# pay-optical.net
KiCad netlist of a schematic drawn in Altium Designer
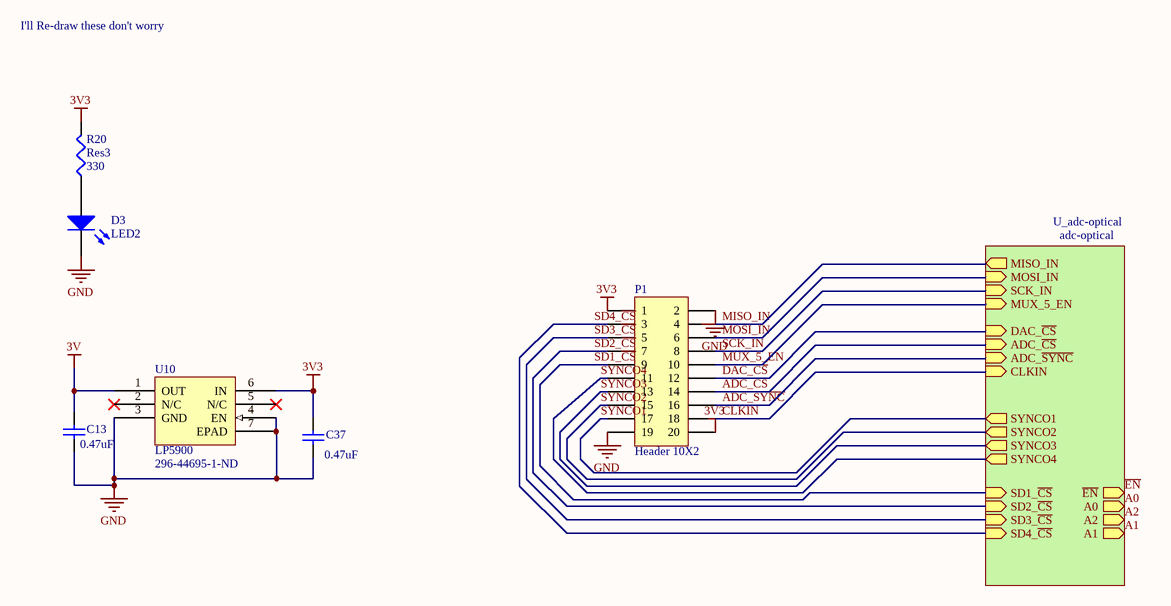
[diagram p0: pay-optical.SchDoc]

(export (version "E")
  (design (tool "Eeschema 10.0.6"))
  (components
    (comp (ref "C13")
      (value "0.47uF")
      (footprint "1608[0603]")
      (description "Capacitor (Semiconductor SIM Model)")
      (fields (field (name "PUBLISHER") "Altium Limited"))
      (libsource (lib "Miscellaneous Devices") (part "Cap Semi"))
    )
    (comp (ref "C37")
      (value "0.47uF")
      (footprint "1608[0603]")
      (description "Capacitor (Semiconductor SIM Model)")
      (fields (field (name "PUBLISHER") "Altium Limited"))
      (libsource (lib "Miscellaneous Devices") (part "Cap Semi"))
    )
    (comp (ref "D3")
      (value "LED2")
      (footprint "0603-LED")
      (description "Typical RED, GREEN, YELLOW, AMBER GaAs LED")
      (fields (field (name "PUBLISHER") "Altium Limited"))
      (libsource (lib "Miscellaneous Devices") (part "LED2"))
    )
    (comp (ref "P1")
      (value "Header 10X2")
      (footprint "CON20_2X10_DUA00")
      (description "Header, 10-Pin, Dual row")
      (fields (field (name "PUBLISHER") "Altium Limited"))
      (libsource (lib "Miscellaneous Connectors") (part "Header 10X2"))
    )
    (comp (ref "R20")
      (value "Res3")
      (footprint "0402")
      (description "Resistor")
      (fields (field (name "ALTIUM_VALUE") "330") (field (name "PUBLISHER") "Altium Limited"))
      (libsource (lib "Miscellaneous Devices") (part "Res3"))
    )
    (comp (ref "U10")
      (value "LP5900")
      (footprint "DFN220X250X80-7N")
      (description "Low noise 3V low dropout regulator for analog and RF applications.")
      (fields (field (name "SUPPLIER PART NUMBER 1") "296-44695-1-ND"))
      (libsource (lib "PAY") (part "LP5900"))
    )
  )
  (nets
    (net (code "4") (name "/ADC_~{CS}") (class "Default")
      (node (ref "P1") (pin "14") (pinfunction "14_14") (pintype "passive"))
    )
    (net (code "5") (name "/ADC_~{SYNC}") (class "Default")
      (node (ref "P1") (pin "16") (pinfunction "16_16") (pintype "passive"))
    )
    (net (code "6") (name "/CLKIN") (class "Default")
      (node (ref "P1") (pin "18") (pinfunction "18_18") (pintype "passive"))
    )
    (net (code "7") (name "/DAC_~{CS}") (class "Default")
      (node (ref "P1") (pin "12") (pinfunction "12_12") (pintype "passive"))
    )
    (net (code "8") (name "/MISO_IN") (class "Default")
      (node (ref "P1") (pin "4") (pinfunction "4_4") (pintype "passive"))
    )
    (net (code "9") (name "/MOSI_IN") (class "Default")
      (node (ref "P1") (pin "6") (pinfunction "6_6") (pintype "passive"))
    )
    (net (code "10") (name "/MUX_5_EN") (class "Default")
      (node (ref "P1") (pin "10") (pinfunction "10_10") (pintype "passive"))
    )
    (net (code "11") (name "/SCK_IN") (class "Default")
      (node (ref "P1") (pin "8") (pinfunction "8_8") (pintype "passive"))
    )
    (net (code "12") (name "/SD1_~{CS}") (class "Default")
      (node (ref "P1") (pin "9") (pinfunction "9_9") (pintype "passive"))
    )
    (net (code "13") (name "/SD2_~{CS}") (class "Default")
      (node (ref "P1") (pin "7") (pinfunction "7_7") (pintype "passive"))
    )
    (net (code "14") (name "/SD3_~{CS}") (class "Default")
      (node (ref "P1") (pin "5") (pinfunction "5_5") (pintype "passive"))
    )
    (net (code "15") (name "/SD4_~{CS}") (class "Default")
      (node (ref "P1") (pin "3") (pinfunction "3_3") (pintype "passive"))
    )
    (net (code "16") (name "/SYNCO1") (class "Default")
      (node (ref "P1") (pin "17") (pinfunction "17_17") (pintype "passive"))
    )
    (net (code "17") (name "/SYNCO2") (class "Default")
      (node (ref "P1") (pin "15") (pinfunction "15_15") (pintype "passive"))
    )
    (net (code "18") (name "/SYNCO3") (class "Default")
      (node (ref "P1") (pin "13") (pinfunction "13_13") (pintype "passive"))
    )
    (net (code "19") (name "/SYNCO4") (class "Default")
      (node (ref "P1") (pin "11") (pinfunction "11_11") (pintype "passive"))
    )
    (net (code "21") (name "3V") (class "Default")
      (node (ref "C13") (pin "2") (pinfunction "2_2") (pintype "passive"))
      (node (ref "U10") (pin "1") (pinfunction "OUT_1") (pintype "power_in"))
    )
    (net (code "22") (name "3V3") (class "Default")
      (node (ref "C37") (pin "2") (pinfunction "2_2") (pintype "passive"))
      (node (ref "P1") (pin "1") (pinfunction "1_1") (pintype "passive"))
      (node (ref "P1") (pin "20") (pinfunction "20_20") (pintype "passive"))
      (node (ref "R20") (pin "2") (pinfunction "2_2") (pintype "passive"))
      (node (ref "U10") (pin "6") (pinfunction "IN_6") (pintype "power_in"))
    )
    (net (code "23") (name "GND") (class "Default")
      (node (ref "C13") (pin "1") (pinfunction "1_1") (pintype "passive"))
      (node (ref "C37") (pin "1") (pinfunction "1_1") (pintype "passive"))
      (node (ref "D3") (pin "2") (pinfunction "K_2") (pintype "passive"))
      (node (ref "P1") (pin "19") (pinfunction "19_19") (pintype "passive"))
      (node (ref "P1") (pin "2") (pinfunction "2_2") (pintype "passive"))
      (node (ref "U10") (pin "3") (pinfunction "GND_3") (pintype "power_in"))
      (node (ref "U10") (pin "4") (pinfunction "EN_4") (pintype "input"))
      (node (ref "U10") (pin "7") (pinfunction "EPAD_7") (pintype "passive"))
    )
    (net (code "24") (name "Net-(D3-A)") (class "Default")
      (node (ref "D3") (pin "1") (pinfunction "A_1") (pintype "passive"))
      (node (ref "R20") (pin "1") (pinfunction "1_1") (pintype "passive"))
    )
    (net (code "25") (name "unconnected-(U10-N{slash}C-Pad2)") (class "Default")
      (node (ref "U10") (pin "2") (pinfunction "N/C_2") (pintype "passive+no_connect"))
    )
    (net (code "26") (name "unconnected-(U10-N{slash}C-Pad5)") (class "Default")
      (node (ref "U10") (pin "5") (pinfunction "N/C_5") (pintype "passive+no_connect"))
    )
  )
)
